# material-sorter.net
KiCad netlist of a schematic drawn in EAGLE
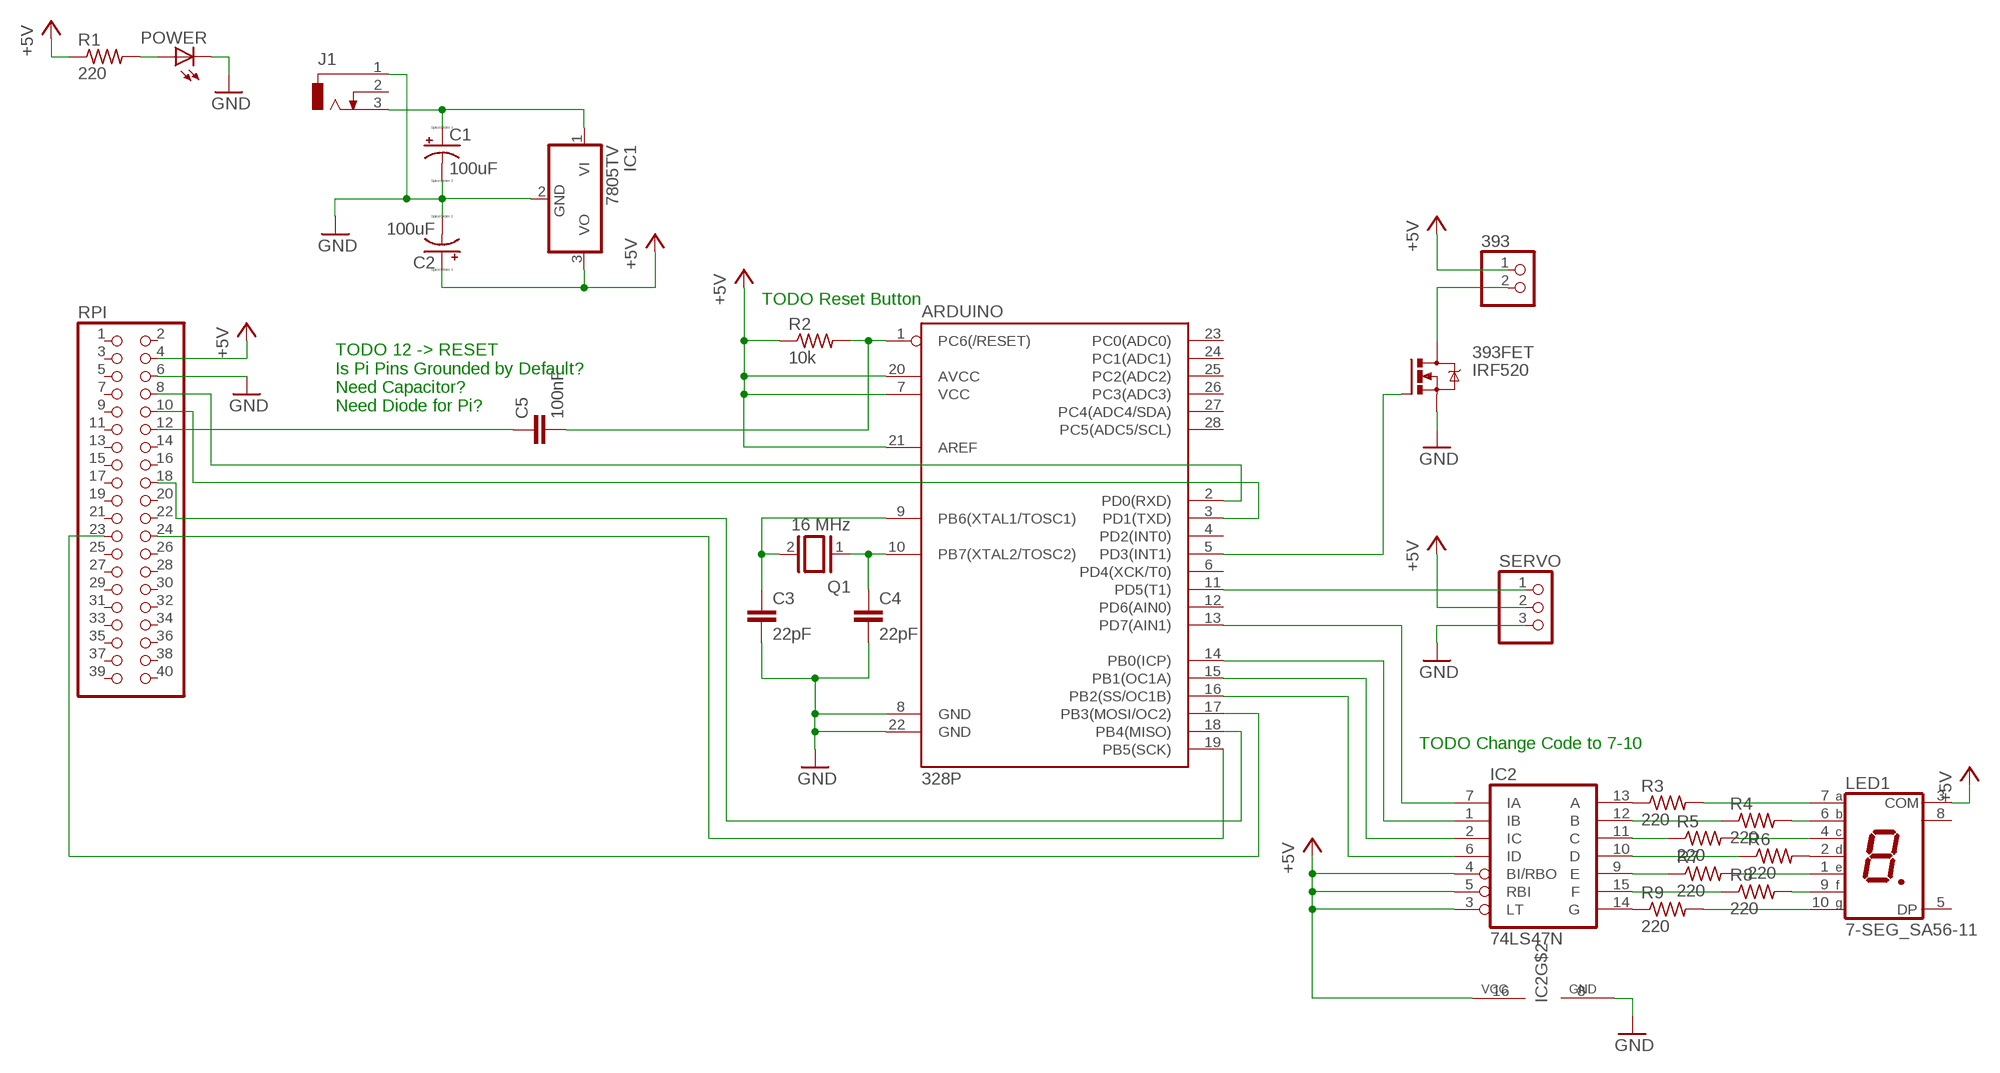
[diagram p0: schematic, sheet 1]

(export (version "E")
  (design (tool "Eeschema 10.0.6"))
  (components
    (comp (ref "393")
      (value "PINHD-1X2")
      (footprint "eagle-import:1X02")
      (libsource (lib "eagle-import") (part "PINHD-1X2"))
    )
    (comp (ref "393FET")
      (value "IRF520")
      (footprint "eagle-import:TO220BV")
      (libsource (lib "eagle-import") (part "IRF520"))
    )
    (comp (ref "ARDUINO")
      (value "328P")
      (footprint "eagle-import:DIP28")
      (libsource (lib "eagle-import") (part "ATMEGA328P_PDIP"))
    )
    (comp (ref "C1")
      (value "100uF")
      (footprint "eagle-import:E2,5-5")
      (libsource (lib "eagle-import") (part "CPOL-USE2.5-5"))
    )
    (comp (ref "C2")
      (value "100uF")
      (footprint "eagle-import:E2,5-5")
      (libsource (lib "eagle-import") (part "CPOL-USE2.5-5"))
    )
    (comp (ref "C3")
      (value "22pF")
      (footprint "eagle-import:C2.5-5")
      (libsource (lib "eagle-import") (part "C2.5/5"))
    )
    (comp (ref "C4")
      (value "22pF")
      (footprint "eagle-import:C2.5-5")
      (libsource (lib "eagle-import") (part "C2.5/5"))
    )
    (comp (ref "C5")
      (value "100nF")
      (footprint "eagle-import:C2.5-5")
      (libsource (lib "eagle-import") (part "C2.5/5"))
    )
    (comp (ref "IC1")
      (value "7805TV")
      (footprint "eagle-import:TO220V")
      (libsource (lib "eagle-import") (part "78TV05"))
    )
    (comp (ref "IC2")
      (value "74LS47N")
      (footprint "eagle-import:DIL16")
      (libsource (lib "eagle-import") (part "7447NLS"))
    )
    (comp (ref "J1")
      (value "DCJ0303")
      (footprint "eagle-import:DCJ0303")
      (libsource (lib "eagle-import") (part "DCJ0303"))
    )
    (comp (ref "LED1")
      (value "7-SEG_SA56-11")
      (footprint "eagle-import:SA56-11")
      (libsource (lib "eagle-import") (part "7-SEG_SA56-11"))
    )
    (comp (ref "POWER")
      (value "LED5MM")
      (footprint "eagle-import:LED5MM")
      (libsource (lib "eagle-import") (part "LED5MM"))
    )
    (comp (ref "Q1")
      (value "16 MHz")
      (footprint "eagle-import:QS")
      (libsource (lib "eagle-import") (part "XTAL/S"))
    )
    (comp (ref "R1")
      (value "220")
      (footprint "eagle-import:0207_2V")
      (libsource (lib "eagle-import") (part "R-US_0207/2V"))
    )
    (comp (ref "R2")
      (value "10k")
      (footprint "eagle-import:0207_2V")
      (libsource (lib "eagle-import") (part "R-US_0207/2V"))
    )
    (comp (ref "R3")
      (value "220")
      (footprint "eagle-import:0207_2V")
      (libsource (lib "eagle-import") (part "R-US_0207/2V"))
    )
    (comp (ref "R4")
      (value "220")
      (footprint "eagle-import:0207_2V")
      (libsource (lib "eagle-import") (part "R-US_0207/2V"))
    )
    (comp (ref "R5")
      (value "220")
      (footprint "eagle-import:0207_2V")
      (libsource (lib "eagle-import") (part "R-US_0207/2V"))
    )
    (comp (ref "R6")
      (value "220")
      (footprint "eagle-import:0207_2V")
      (libsource (lib "eagle-import") (part "R-US_0207/2V"))
    )
    (comp (ref "R7")
      (value "220")
      (footprint "eagle-import:0207_2V")
      (libsource (lib "eagle-import") (part "R-US_0207/2V"))
    )
    (comp (ref "R8")
      (value "220")
      (footprint "eagle-import:0207_2V")
      (libsource (lib "eagle-import") (part "R-US_0207/2V"))
    )
    (comp (ref "R9")
      (value "220")
      (footprint "eagle-import:0207_2V")
      (libsource (lib "eagle-import") (part "R-US_0207/2V"))
    )
    (comp (ref "RPI")
      (value "PINHD-2X20")
      (footprint "eagle-import:2X20")
      (libsource (lib "eagle-import") (part "PINHD-2X20"))
    )
    (comp (ref "SERVO")
      (value "PINHD-1X3")
      (footprint "eagle-import:1X03")
      (libsource (lib "eagle-import") (part "PINHD-1X3"))
    )
  )
  (nets
    (net (code "1") (name "+5V") (class "Default")
      (node (ref "393") (pin "1") (pinfunction "1_1") (pintype "passive"))
      (node (ref "ARDUINO") (pin "20") (pinfunction "AVCC_20") (pintype "bidirectional"))
      (node (ref "ARDUINO") (pin "21") (pinfunction "AREF_21") (pintype "bidirectional"))
      (node (ref "ARDUINO") (pin "7") (pinfunction "VCC_7") (pintype "bidirectional"))
      (node (ref "C2") (pin "+") (pinfunction "+_+") (pintype "passive"))
      (node (ref "IC1") (pin "3") (pinfunction "VO_3") (pintype "passive"))
      (node (ref "IC2") (pin "16") (pinfunction "VCC_16") (pintype "power_in"))
      (node (ref "IC2") (pin "3") (pinfunction "LT_3") (pintype "input"))
      (node (ref "IC2") (pin "4") (pinfunction "BI/RBO_4") (pintype "input"))
      (node (ref "IC2") (pin "5") (pinfunction "RBI_5") (pintype "input"))
      (node (ref "LED1") (pin "3") (pinfunction "COM_3") (pintype "passive"))
      (node (ref "R1") (pin "1") (pinfunction "1_1") (pintype "passive"))
      (node (ref "R2") (pin "1") (pinfunction "1_1") (pintype "passive"))
      (node (ref "RPI") (pin "4") (pinfunction "4_4") (pintype "passive"))
      (node (ref "SERVO") (pin "2") (pinfunction "2_2") (pintype "passive"))
    )
    (net (code "2") (name "GND") (class "Default")
      (node (ref "393FET") (pin "S") (pinfunction "S_S") (pintype "passive"))
      (node (ref "ARDUINO") (pin "22") (pinfunction "GND_22") (pintype "bidirectional"))
      (node (ref "ARDUINO") (pin "8") (pinfunction "GND_8") (pintype "bidirectional"))
      (node (ref "C1") (pin "-") (pinfunction "-_-") (pintype "passive"))
      (node (ref "C2") (pin "-") (pinfunction "-_-") (pintype "passive"))
      (node (ref "C3") (pin "2") (pinfunction "2_2") (pintype "passive"))
      (node (ref "C4") (pin "2") (pinfunction "2_2") (pintype "passive"))
      (node (ref "IC1") (pin "2") (pinfunction "GND_2") (pintype "passive"))
      (node (ref "IC2") (pin "8") (pinfunction "GND_8") (pintype "power_in"))
      (node (ref "J1") (pin "1") (pinfunction "1_1") (pintype "passive"))
      (node (ref "POWER") (pin "K") (pinfunction "C_K") (pintype "passive"))
      (node (ref "RPI") (pin "6") (pinfunction "6_6") (pintype "passive"))
      (node (ref "SERVO") (pin "3") (pinfunction "3_3") (pintype "passive"))
    )
    (net (code "3") (name "Net-(393-Pad2)") (class "Default")
      (node (ref "393") (pin "2") (pinfunction "2_2") (pintype "passive"))
      (node (ref "393FET") (pin "D") (pinfunction "D_D") (pintype "passive"))
    )
    (net (code "4") (name "Net-(ARDUINO-PB0(ICP))") (class "Default")
      (node (ref "ARDUINO") (pin "14") (pinfunction "PB0(ICP)_14") (pintype "bidirectional"))
      (node (ref "IC2") (pin "1") (pinfunction "IB_1") (pintype "input"))
    )
    (net (code "5") (name "Net-(ARDUINO-PB1(OC1A))") (class "Default")
      (node (ref "ARDUINO") (pin "15") (pinfunction "PB1(OC1A)_15") (pintype "bidirectional"))
      (node (ref "IC2") (pin "2") (pinfunction "IC_2") (pintype "input"))
    )
    (net (code "6") (name "Net-(ARDUINO-PB2(SS{slash}OC1B))") (class "Default")
      (node (ref "ARDUINO") (pin "16") (pinfunction "PB2(SS/OC1B)_16") (pintype "bidirectional"))
      (node (ref "IC2") (pin "6") (pinfunction "ID_6") (pintype "input"))
    )
    (net (code "7") (name "Net-(ARDUINO-PB3(MOSI{slash}OC2))") (class "Default")
      (node (ref "ARDUINO") (pin "17") (pinfunction "PB3(MOSI/OC2)_17") (pintype "bidirectional"))
      (node (ref "RPI") (pin "23") (pinfunction "23_23") (pintype "passive"))
    )
    (net (code "8") (name "Net-(ARDUINO-PB4(MISO))") (class "Default")
      (node (ref "ARDUINO") (pin "18") (pinfunction "PB4(MISO)_18") (pintype "bidirectional"))
      (node (ref "RPI") (pin "18") (pinfunction "18_18") (pintype "passive"))
    )
    (net (code "9") (name "Net-(ARDUINO-PB5(SCK))") (class "Default")
      (node (ref "ARDUINO") (pin "19") (pinfunction "PB5(SCK)_19") (pintype "bidirectional"))
      (node (ref "RPI") (pin "24") (pinfunction "24_24") (pintype "passive"))
    )
    (net (code "10") (name "Net-(ARDUINO-PB6(XTAL1{slash}TOSC1))") (class "Default")
      (node (ref "ARDUINO") (pin "9") (pinfunction "PB6(XTAL1/TOSC1)_9") (pintype "bidirectional"))
      (node (ref "C3") (pin "1") (pinfunction "1_1") (pintype "passive"))
      (node (ref "Q1") (pin "2") (pinfunction "2_2") (pintype "passive"))
    )
    (net (code "11") (name "Net-(ARDUINO-PB7(XTAL2{slash}TOSC2))") (class "Default")
      (node (ref "ARDUINO") (pin "10") (pinfunction "PB7(XTAL2/TOSC2)_10") (pintype "bidirectional"))
      (node (ref "C4") (pin "1") (pinfunction "1_1") (pintype "passive"))
      (node (ref "Q1") (pin "1") (pinfunction "1_1") (pintype "passive"))
    )
    (net (code "12") (name "Net-(ARDUINO-PC6({slash}RESET))") (class "Default")
      (node (ref "ARDUINO") (pin "1") (pinfunction "PC6(/RESET)_1") (pintype "bidirectional"))
      (node (ref "C5") (pin "2") (pinfunction "2_2") (pintype "passive"))
      (node (ref "R2") (pin "2") (pinfunction "2_2") (pintype "passive"))
    )
    (net (code "13") (name "Net-(ARDUINO-PD0(RXD))") (class "Default")
      (node (ref "ARDUINO") (pin "2") (pinfunction "PD0(RXD)_2") (pintype "bidirectional"))
      (node (ref "RPI") (pin "8") (pinfunction "8_8") (pintype "passive"))
    )
    (net (code "14") (name "Net-(ARDUINO-PD1(TXD))") (class "Default")
      (node (ref "ARDUINO") (pin "3") (pinfunction "PD1(TXD)_3") (pintype "bidirectional"))
      (node (ref "RPI") (pin "10") (pinfunction "10_10") (pintype "passive"))
    )
    (net (code "15") (name "Net-(ARDUINO-PD3(INT1))") (class "Default")
      (node (ref "393FET") (pin "G") (pinfunction "G_G") (pintype "passive"))
      (node (ref "ARDUINO") (pin "5") (pinfunction "PD3(INT1)_5") (pintype "bidirectional"))
    )
    (net (code "16") (name "Net-(ARDUINO-PD5(T1))") (class "Default")
      (node (ref "ARDUINO") (pin "11") (pinfunction "PD5(T1)_11") (pintype "bidirectional"))
      (node (ref "SERVO") (pin "1") (pinfunction "1_1") (pintype "passive"))
    )
    (net (code "17") (name "Net-(ARDUINO-PD7(AIN1))") (class "Default")
      (node (ref "ARDUINO") (pin "13") (pinfunction "PD7(AIN1)_13") (pintype "bidirectional"))
      (node (ref "IC2") (pin "7") (pinfunction "IA_7") (pintype "input"))
    )
    (net (code "18") (name "Net-(C5-Pad1)") (class "Default")
      (node (ref "C5") (pin "1") (pinfunction "1_1") (pintype "passive"))
      (node (ref "RPI") (pin "12") (pinfunction "12_12") (pintype "passive"))
    )
    (net (code "19") (name "Net-(IC1-VI)") (class "Default")
      (node (ref "C1") (pin "+") (pinfunction "+_+") (pintype "passive"))
      (node (ref "IC1") (pin "1") (pinfunction "VI_1") (pintype "input"))
      (node (ref "J1") (pin "3") (pinfunction "3_3") (pintype "passive"))
    )
    (net (code "20") (name "Net-(IC2A-A)") (class "Default")
      (node (ref "IC2") (pin "13") (pinfunction "A_13") (pintype "output"))
      (node (ref "R3") (pin "1") (pinfunction "1_1") (pintype "passive"))
    )
    (net (code "21") (name "Net-(IC2A-B)") (class "Default")
      (node (ref "IC2") (pin "12") (pinfunction "B_12") (pintype "output"))
      (node (ref "R4") (pin "1") (pinfunction "1_1") (pintype "passive"))
    )
    (net (code "22") (name "Net-(IC2A-C)") (class "Default")
      (node (ref "IC2") (pin "11") (pinfunction "C_11") (pintype "output"))
      (node (ref "R5") (pin "1") (pinfunction "1_1") (pintype "passive"))
    )
    (net (code "23") (name "Net-(IC2A-D)") (class "Default")
      (node (ref "IC2") (pin "10") (pinfunction "D_10") (pintype "output"))
      (node (ref "R6") (pin "1") (pinfunction "1_1") (pintype "passive"))
    )
    (net (code "24") (name "Net-(IC2A-E)") (class "Default")
      (node (ref "IC2") (pin "9") (pinfunction "E_9") (pintype "output"))
      (node (ref "R7") (pin "1") (pinfunction "1_1") (pintype "passive"))
    )
    (net (code "25") (name "Net-(IC2A-F)") (class "Default")
      (node (ref "IC2") (pin "15") (pinfunction "F_15") (pintype "output"))
      (node (ref "R8") (pin "1") (pinfunction "1_1") (pintype "passive"))
    )
    (net (code "26") (name "Net-(IC2A-G)") (class "Default")
      (node (ref "IC2") (pin "14") (pinfunction "G_14") (pintype "output"))
      (node (ref "R9") (pin "1") (pinfunction "1_1") (pintype "passive"))
    )
    (net (code "27") (name "Net-(LED1-A)") (class "Default")
      (node (ref "LED1") (pin "7") (pinfunction "A_7") (pintype "passive"))
      (node (ref "R3") (pin "2") (pinfunction "2_2") (pintype "passive"))
    )
    (net (code "28") (name "Net-(LED1-B)") (class "Default")
      (node (ref "LED1") (pin "6") (pinfunction "B_6") (pintype "passive"))
      (node (ref "R4") (pin "2") (pinfunction "2_2") (pintype "passive"))
    )
    (net (code "29") (name "Net-(LED1-C)") (class "Default")
      (node (ref "LED1") (pin "4") (pinfunction "C_4") (pintype "passive"))
      (node (ref "R5") (pin "2") (pinfunction "2_2") (pintype "passive"))
    )
    (net (code "30") (name "Net-(LED1-D)") (class "Default")
      (node (ref "LED1") (pin "2") (pinfunction "D_2") (pintype "passive"))
      (node (ref "R6") (pin "2") (pinfunction "2_2") (pintype "passive"))
    )
    (net (code "31") (name "Net-(LED1-E)") (class "Default")
      (node (ref "LED1") (pin "1") (pinfunction "E_1") (pintype "passive"))
      (node (ref "R7") (pin "2") (pinfunction "2_2") (pintype "passive"))
    )
    (net (code "32") (name "Net-(LED1-F)") (class "Default")
      (node (ref "LED1") (pin "9") (pinfunction "F_9") (pintype "passive"))
      (node (ref "R8") (pin "2") (pinfunction "2_2") (pintype "passive"))
    )
    (net (code "33") (name "Net-(LED1-G)") (class "Default")
      (node (ref "LED1") (pin "10") (pinfunction "G_10") (pintype "passive"))
      (node (ref "R9") (pin "2") (pinfunction "2_2") (pintype "passive"))
    )
    (net (code "34") (name "Net-(POWER-PadA)") (class "Default")
      (node (ref "POWER") (pin "A") (pinfunction "A_A") (pintype "passive"))
      (node (ref "R1") (pin "2") (pinfunction "2_2") (pintype "passive"))
    )
    (net (code "35") (name "unconnected-(ARDUINO-PC0(ADC0)-Pad23)") (class "Default")
      (node (ref "ARDUINO") (pin "23") (pinfunction "PC0(ADC0)_23") (pintype "bidirectional"))
    )
    (net (code "36") (name "unconnected-(ARDUINO-PC1(ADC1)-Pad24)") (class "Default")
      (node (ref "ARDUINO") (pin "24") (pinfunction "PC1(ADC1)_24") (pintype "bidirectional"))
    )
    (net (code "37") (name "unconnected-(ARDUINO-PC2(ADC2)-Pad25)") (class "Default")
      (node (ref "ARDUINO") (pin "25") (pinfunction "PC2(ADC2)_25") (pintype "bidirectional"))
    )
    (net (code "38") (name "unconnected-(ARDUINO-PC3(ADC3)-Pad26)") (class "Default")
      (node (ref "ARDUINO") (pin "26") (pinfunction "PC3(ADC3)_26") (pintype "bidirectional"))
    )
    (net (code "39") (name "unconnected-(ARDUINO-PC4(ADC4{slash}SDA)-Pad27)") (class "Default")
      (node (ref "ARDUINO") (pin "27") (pinfunction "PC4(ADC4/SDA)_27") (pintype "bidirectional"))
    )
    (net (code "40") (name "unconnected-(ARDUINO-PC5(ADC5{slash}SCL)-Pad28)") (class "Default")
      (node (ref "ARDUINO") (pin "28") (pinfunction "PC5(ADC5/SCL)_28") (pintype "bidirectional"))
    )
    (net (code "41") (name "unconnected-(ARDUINO-PD2(INT0)-Pad4)") (class "Default")
      (node (ref "ARDUINO") (pin "4") (pinfunction "PD2(INT0)_4") (pintype "bidirectional"))
    )
    (net (code "42") (name "unconnected-(ARDUINO-PD4(XCK{slash}T0)-Pad6)") (class "Default")
      (node (ref "ARDUINO") (pin "6") (pinfunction "PD4(XCK/T0)_6") (pintype "bidirectional"))
    )
    (net (code "43") (name "unconnected-(ARDUINO-PD6(AIN0)-Pad12)") (class "Default")
      (node (ref "ARDUINO") (pin "12") (pinfunction "PD6(AIN0)_12") (pintype "bidirectional"))
    )
    (net (code "44") (name "unconnected-(J1-Pad2)") (class "Default")
      (node (ref "J1") (pin "2") (pinfunction "2_2") (pintype "passive"))
    )
    (net (code "45") (name "unconnected-(LED1-COM-Pad8)") (class "Default")
      (node (ref "LED1") (pin "8") (pinfunction "COM_8") (pintype "passive"))
    )
    (net (code "46") (name "unconnected-(LED1-DP-Pad5)") (class "Default")
      (node (ref "LED1") (pin "5") (pinfunction "DP_5") (pintype "passive"))
    )
    (net (code "47") (name "unconnected-(RPI-Pad1)") (class "Default")
      (node (ref "RPI") (pin "1") (pinfunction "1_1") (pintype "passive"))
    )
    (net (code "48") (name "unconnected-(RPI-Pad2)") (class "Default")
      (node (ref "RPI") (pin "2") (pinfunction "2_2") (pintype "passive"))
    )
    (net (code "49") (name "unconnected-(RPI-Pad3)") (class "Default")
      (node (ref "RPI") (pin "3") (pinfunction "3_3") (pintype "passive"))
    )
    (net (code "50") (name "unconnected-(RPI-Pad5)") (class "Default")
      (node (ref "RPI") (pin "5") (pinfunction "5_5") (pintype "passive"))
    )
    (net (code "51") (name "unconnected-(RPI-Pad7)") (class "Default")
      (node (ref "RPI") (pin "7") (pinfunction "7_7") (pintype "passive"))
    )
    (net (code "52") (name "unconnected-(RPI-Pad9)") (class "Default")
      (node (ref "RPI") (pin "9") (pinfunction "9_9") (pintype "passive"))
    )
    (net (code "53") (name "unconnected-(RPI-Pad11)") (class "Default")
      (node (ref "RPI") (pin "11") (pinfunction "11_11") (pintype "passive"))
    )
    (net (code "54") (name "unconnected-(RPI-Pad13)") (class "Default")
      (node (ref "RPI") (pin "13") (pinfunction "13_13") (pintype "passive"))
    )
    (net (code "55") (name "unconnected-(RPI-Pad14)") (class "Default")
      (node (ref "RPI") (pin "14") (pinfunction "14_14") (pintype "passive"))
    )
    (net (code "56") (name "unconnected-(RPI-Pad15)") (class "Default")
      (node (ref "RPI") (pin "15") (pinfunction "15_15") (pintype "passive"))
    )
    (net (code "57") (name "unconnected-(RPI-Pad16)") (class "Default")
      (node (ref "RPI") (pin "16") (pinfunction "16_16") (pintype "passive"))
    )
    (net (code "58") (name "unconnected-(RPI-Pad17)") (class "Default")
      (node (ref "RPI") (pin "17") (pinfunction "17_17") (pintype "passive"))
    )
    (net (code "59") (name "unconnected-(RPI-Pad19)") (class "Default")
      (node (ref "RPI") (pin "19") (pinfunction "19_19") (pintype "passive"))
    )
    (net (code "60") (name "unconnected-(RPI-Pad20)") (class "Default")
      (node (ref "RPI") (pin "20") (pinfunction "20_20") (pintype "passive"))
    )
    (net (code "61") (name "unconnected-(RPI-Pad21)") (class "Default")
      (node (ref "RPI") (pin "21") (pinfunction "21_21") (pintype "passive"))
    )
    (net (code "62") (name "unconnected-(RPI-Pad22)") (class "Default")
      (node (ref "RPI") (pin "22") (pinfunction "22_22") (pintype "passive"))
    )
    (net (code "63") (name "unconnected-(RPI-Pad25)") (class "Default")
      (node (ref "RPI") (pin "25") (pinfunction "25_25") (pintype "passive"))
    )
    (net (code "64") (name "unconnected-(RPI-Pad26)") (class "Default")
      (node (ref "RPI") (pin "26") (pinfunction "26_26") (pintype "passive"))
    )
    (net (code "65") (name "unconnected-(RPI-Pad27)") (class "Default")
      (node (ref "RPI") (pin "27") (pinfunction "27_27") (pintype "passive"))
    )
    (net (code "66") (name "unconnected-(RPI-Pad28)") (class "Default")
      (node (ref "RPI") (pin "28") (pinfunction "28_28") (pintype "passive"))
    )
    (net (code "67") (name "unconnected-(RPI-Pad29)") (class "Default")
      (node (ref "RPI") (pin "29") (pinfunction "29_29") (pintype "passive"))
    )
    (net (code "68") (name "unconnected-(RPI-Pad30)") (class "Default")
      (node (ref "RPI") (pin "30") (pinfunction "30_30") (pintype "passive"))
    )
    (net (code "69") (name "unconnected-(RPI-Pad31)") (class "Default")
      (node (ref "RPI") (pin "31") (pinfunction "31_31") (pintype "passive"))
    )
    (net (code "70") (name "unconnected-(RPI-Pad32)") (class "Default")
      (node (ref "RPI") (pin "32") (pinfunction "32_32") (pintype "passive"))
    )
    (net (code "71") (name "unconnected-(RPI-Pad33)") (class "Default")
      (node (ref "RPI") (pin "33") (pinfunction "33_33") (pintype "passive"))
    )
    (net (code "72") (name "unconnected-(RPI-Pad34)") (class "Default")
      (node (ref "RPI") (pin "34") (pinfunction "34_34") (pintype "passive"))
    )
    (net (code "73") (name "unconnected-(RPI-Pad35)") (class "Default")
      (node (ref "RPI") (pin "35") (pinfunction "35_35") (pintype "passive"))
    )
    (net (code "74") (name "unconnected-(RPI-Pad36)") (class "Default")
      (node (ref "RPI") (pin "36") (pinfunction "36_36") (pintype "passive"))
    )
    (net (code "75") (name "unconnected-(RPI-Pad37)") (class "Default")
      (node (ref "RPI") (pin "37") (pinfunction "37_37") (pintype "passive"))
    )
    (net (code "76") (name "unconnected-(RPI-Pad38)") (class "Default")
      (node (ref "RPI") (pin "38") (pinfunction "38_38") (pintype "passive"))
    )
    (net (code "77") (name "unconnected-(RPI-Pad39)") (class "Default")
      (node (ref "RPI") (pin "39") (pinfunction "39_39") (pintype "passive"))
    )
    (net (code "78") (name "unconnected-(RPI-Pad40)") (class "Default")
      (node (ref "RPI") (pin "40") (pinfunction "40_40") (pintype "passive"))
    )
  )
)
